# Mega2560_SX_Shield.net
KiCad netlist of a schematic drawn in EAGLE
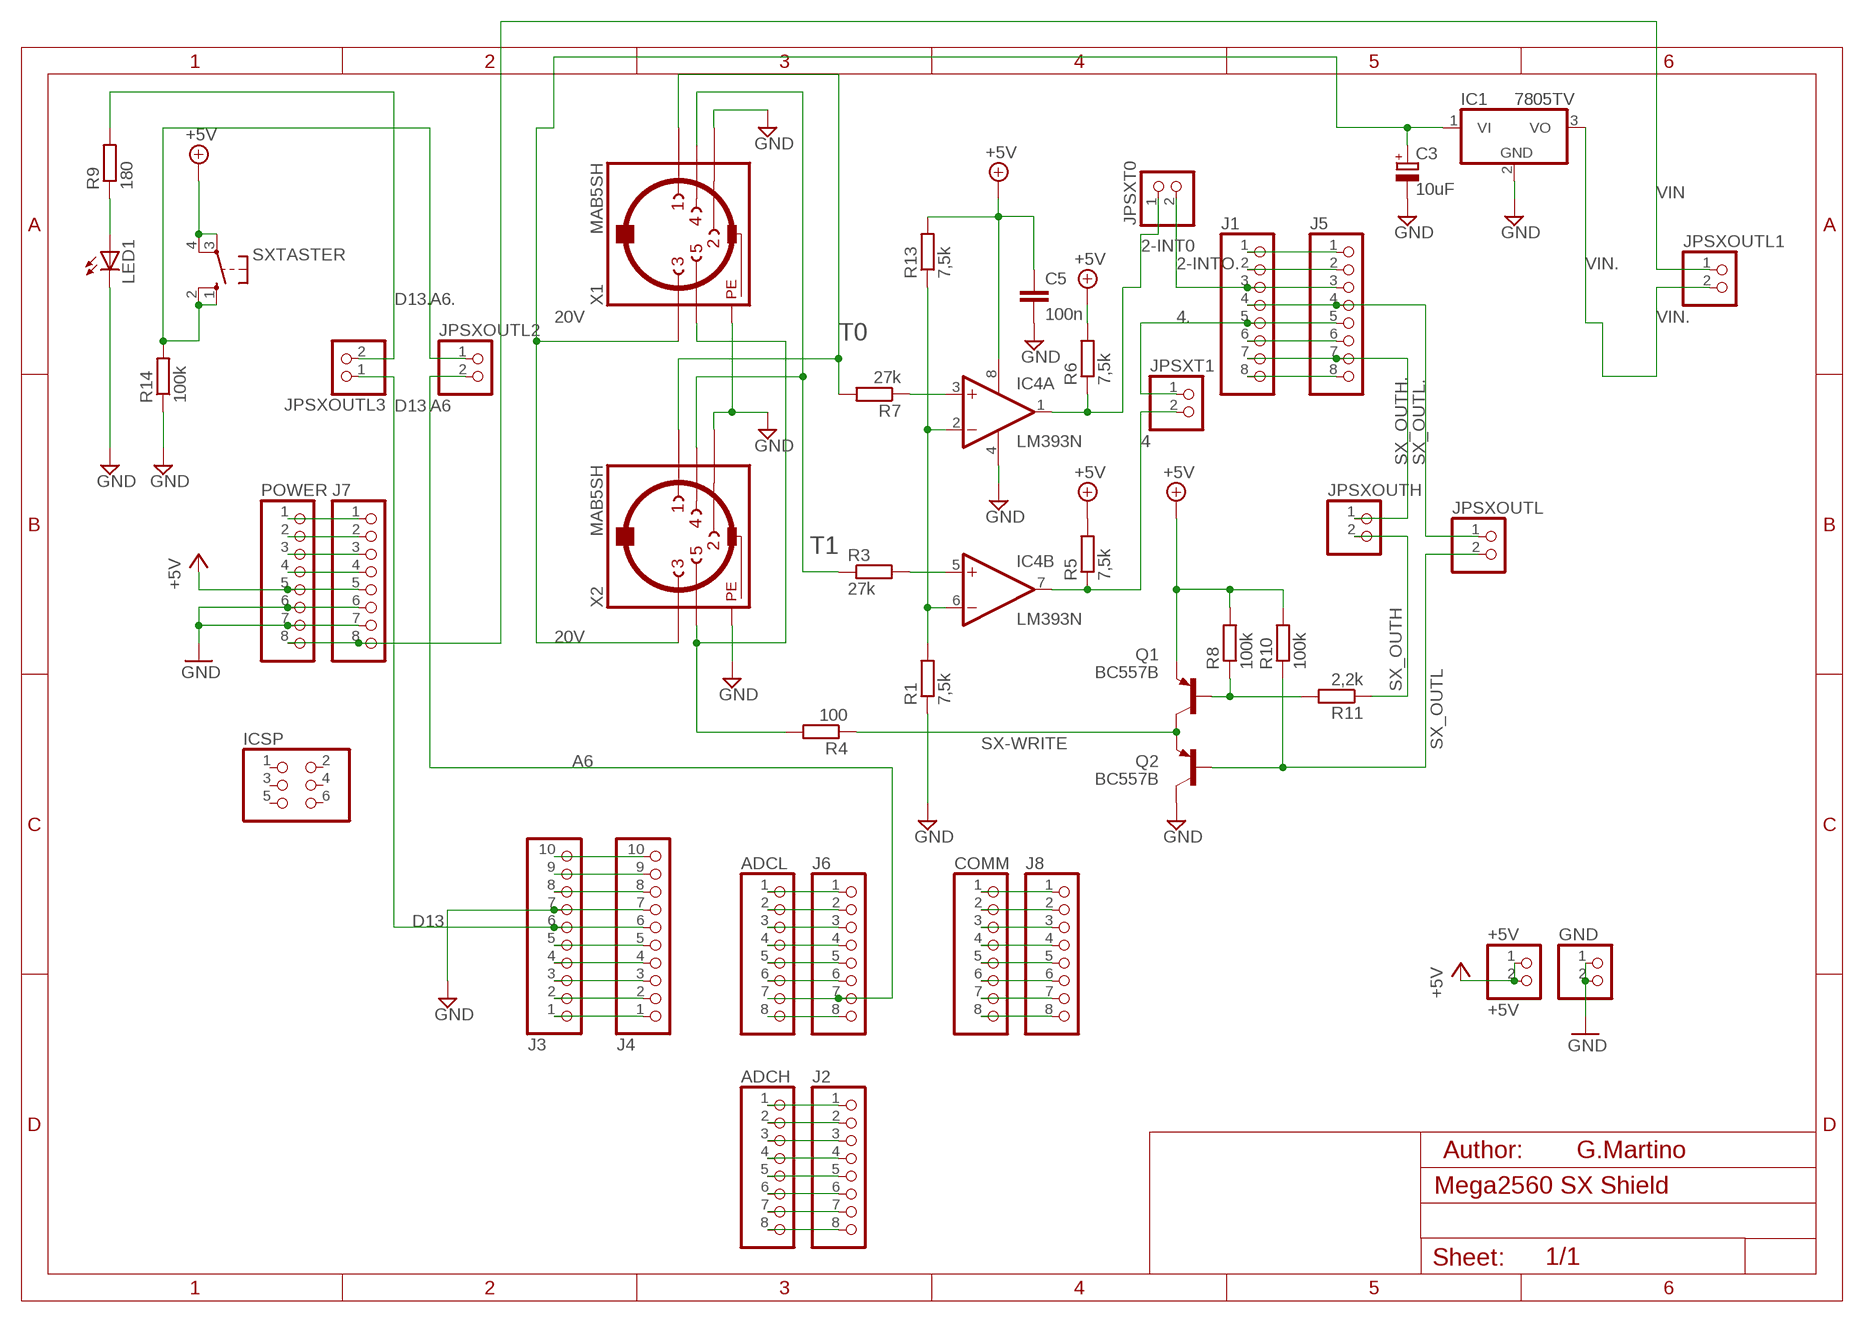
[diagram p0: schematic, sheet 1]

(export (version "E")
  (design (tool "Eeschema 10.0.6"))
  (components
    (comp (ref "+5V")
      (value "+5V")
      (footprint "eagle-import:1X02")
      (libsource (lib "eagle-import") (part "PINHD-1X2"))
    )
    (comp (ref "ADCH")
      (value "PINHD-1X8TH")
      (footprint "eagle-import:1X08-TH")
      (libsource (lib "eagle-import") (part "PINHD-1X8TH"))
    )
    (comp (ref "ADCL")
      (value "PINHD-1X8TH")
      (footprint "eagle-import:1X08-TH")
      (libsource (lib "eagle-import") (part "PINHD-1X8TH"))
    )
    (comp (ref "C3")
      (value "10uF")
      (footprint "eagle-import:TT2D5")
      (libsource (lib "eagle-import") (part "CPOL-EUTT2D5"))
    )
    (comp (ref "C5")
      (value "100n")
      (footprint "eagle-import:C050-025X075")
      (libsource (lib "eagle-import") (part "C-EU050-025X075"))
    )
    (comp (ref "COMM")
      (value "PINHD-1X8TH")
      (footprint "eagle-import:1X08-TH")
      (libsource (lib "eagle-import") (part "PINHD-1X8TH"))
    )
    (comp (ref "GND")
      (value "PINHD-1X2")
      (footprint "eagle-import:1X02")
      (libsource (lib "eagle-import") (part "PINHD-1X2"))
    )
    (comp (ref "IC1")
      (value "7805TV")
      (footprint "eagle-import:TO220V")
      (libsource (lib "eagle-import") (part "78TV05"))
    )
    (comp (ref "IC4")
      (value "LM393N")
      (footprint "eagle-import:DIL08")
      (libsource (lib "eagle-import") (part "LM393N"))
    )
    (comp (ref "ICSP")
      (value "PINHD-2X3")
      (footprint "eagle-import:2X03")
      (libsource (lib "eagle-import") (part "PINHD-2X3"))
    )
    (comp (ref "J1")
      (value "PINHD-1X8TH")
      (footprint "eagle-import:1X08-TH")
      (libsource (lib "eagle-import") (part "PINHD-1X8TH"))
    )
    (comp (ref "J2")
      (value "PINHD-1X8TH")
      (footprint "eagle-import:1X08-TH")
      (libsource (lib "eagle-import") (part "PINHD-1X8TH"))
    )
    (comp (ref "J3")
      (value "PINHD-1X10TH")
      (footprint "eagle-import:1X10-TH")
      (libsource (lib "eagle-import") (part "PINHD-1X10TH"))
    )
    (comp (ref "J4")
      (value "PINHD-1X10TH")
      (footprint "eagle-import:1X10-TH")
      (libsource (lib "eagle-import") (part "PINHD-1X10TH"))
    )
    (comp (ref "J5")
      (value "PINHD-1X8TH")
      (footprint "eagle-import:1X08-TH")
      (libsource (lib "eagle-import") (part "PINHD-1X8TH"))
    )
    (comp (ref "J6")
      (value "PINHD-1X8TH")
      (footprint "eagle-import:1X08-TH")
      (libsource (lib "eagle-import") (part "PINHD-1X8TH"))
    )
    (comp (ref "J7")
      (value "PINHD-1X8TH")
      (footprint "eagle-import:1X08-TH")
      (libsource (lib "eagle-import") (part "PINHD-1X8TH"))
    )
    (comp (ref "J8")
      (value "PINHD-1X8TH")
      (footprint "eagle-import:1X08-TH")
      (libsource (lib "eagle-import") (part "PINHD-1X8TH"))
    )
    (comp (ref "JPSXOUTH")
      (value "PINHD-1X2")
      (footprint "eagle-import:1X02")
      (libsource (lib "eagle-import") (part "PINHD-1X2"))
    )
    (comp (ref "JPSXOUTL")
      (value "PINHD-1X2")
      (footprint "eagle-import:1X02")
      (libsource (lib "eagle-import") (part "PINHD-1X2"))
    )
    (comp (ref "JPSXOUTL1")
      (value "PINHD-1X2")
      (footprint "eagle-import:1X02")
      (libsource (lib "eagle-import") (part "PINHD-1X2"))
    )
    (comp (ref "JPSXOUTL2")
      (value "PINHD-1X2")
      (footprint "eagle-import:1X02")
      (libsource (lib "eagle-import") (part "PINHD-1X2"))
    )
    (comp (ref "JPSXOUTL3")
      (value "PINHD-1X2")
      (footprint "eagle-import:1X02")
      (libsource (lib "eagle-import") (part "PINHD-1X2"))
    )
    (comp (ref "JPSXT0")
      (value "PINHD-1X2")
      (footprint "eagle-import:1X02")
      (libsource (lib "eagle-import") (part "PINHD-1X2"))
    )
    (comp (ref "JPSXT1")
      (value "PINHD-1X2")
      (footprint "eagle-import:1X02")
      (libsource (lib "eagle-import") (part "PINHD-1X2"))
    )
    (comp (ref "LED1")
      (value "LED3MM")
      (footprint "eagle-import:LED3MM")
      (libsource (lib "eagle-import") (part "LED3MM"))
    )
    (comp (ref "POWER")
      (value "PINHD-1X8TH")
      (footprint "eagle-import:1X08-TH")
      (libsource (lib "eagle-import") (part "PINHD-1X8TH"))
    )
    (comp (ref "Q1")
      (value "BC557B")
      (footprint "eagle-import:TO92-EBC")
      (libsource (lib "eagle-import") (part "BC557B"))
    )
    (comp (ref "Q2")
      (value "BC557B")
      (footprint "eagle-import:TO92-EBC")
      (libsource (lib "eagle-import") (part "BC557B"))
    )
    (comp (ref "R1")
      (value "7,5k")
      (footprint "eagle-import:0207_10")
      (libsource (lib "eagle-import") (part "rcl_334_R-EU_0207/10"))
    )
    (comp (ref "R3")
      (value "27k")
      (footprint "eagle-import:0207_10")
      (libsource (lib "eagle-import") (part "R-EU_0207/10"))
    )
    (comp (ref "R4")
      (value "100")
      (footprint "eagle-import:0207_10")
      (libsource (lib "eagle-import") (part "rcl_334_R-EU_0207/10"))
    )
    (comp (ref "R5")
      (value "7,5k")
      (footprint "eagle-import:0207_10")
      (libsource (lib "eagle-import") (part "rcl_334_R-EU_0207/10"))
    )
    (comp (ref "R6")
      (value "7,5k")
      (footprint "eagle-import:0207_10")
      (libsource (lib "eagle-import") (part "rcl_334_R-EU_0207/10"))
    )
    (comp (ref "R7")
      (value "27k")
      (footprint "eagle-import:0207_10")
      (libsource (lib "eagle-import") (part "rcl_334_R-EU_0207/10"))
    )
    (comp (ref "R8")
      (value "100k")
      (footprint "eagle-import:0207_10")
      (libsource (lib "eagle-import") (part "rcl_334_R-EU_0207/10"))
    )
    (comp (ref "R9")
      (value "180")
      (footprint "eagle-import:0207_10")
      (libsource (lib "eagle-import") (part "rcl_334_R-EU_0207/10"))
    )
    (comp (ref "R10")
      (value "100k")
      (footprint "eagle-import:0207_10")
      (libsource (lib "eagle-import") (part "rcl_334_R-EU_0207/10"))
    )
    (comp (ref "R11")
      (value "2,2k")
      (footprint "eagle-import:0207_10")
      (libsource (lib "eagle-import") (part "rcl_334_R-EU_0207/10"))
    )
    (comp (ref "R13")
      (value "7,5k")
      (footprint "eagle-import:0207_10")
      (libsource (lib "eagle-import") (part "rcl_334_R-EU_0207/10"))
    )
    (comp (ref "R14")
      (value "100k")
      (footprint "eagle-import:0207_10")
      (libsource (lib "eagle-import") (part "rcl_334_R-EU_0207/10"))
    )
    (comp (ref "SXTASTER")
      (value "10-XX")
      (footprint "eagle-import:B3F-10XX")
      (fields (field (name "MPN") "B3F-1000"))
      (libsource (lib "eagle-import") (part "10-XX"))
    )
    (comp (ref "X1")
      (value "MAB5SH")
      (footprint "eagle-import:MAB5SH")
      (libsource (lib "eagle-import") (part "MAB5SH"))
    )
    (comp (ref "X2")
      (value "MAB5SH")
      (footprint "eagle-import:MAB5SH")
      (libsource (lib "eagle-import") (part "MAB5SH"))
    )
  )
  (nets
    (net (code "1") (name "+5V") (class "Default")
      (node (ref "+5V") (pin "1") (pinfunction "1_1") (pintype "passive"))
      (node (ref "+5V") (pin "2") (pinfunction "2_2") (pintype "passive"))
      (node (ref "C5") (pin "1") (pinfunction "1_1") (pintype "passive"))
      (node (ref "IC4") (pin "8") (pinfunction "V+_8") (pintype "power_in"))
      (node (ref "J7") (pin "5") (pinfunction "5_5") (pintype "passive"))
      (node (ref "POWER") (pin "5") (pinfunction "5_5") (pintype "passive"))
      (node (ref "Q1") (pin "E") (pinfunction "E_E") (pintype "passive"))
      (node (ref "R10") (pin "2") (pinfunction "2_2") (pintype "passive"))
      (node (ref "R13") (pin "2") (pinfunction "2_2") (pintype "passive"))
      (node (ref "R5") (pin "2") (pinfunction "2_2") (pintype "passive"))
      (node (ref "R6") (pin "2") (pinfunction "2_2") (pintype "passive"))
      (node (ref "R8") (pin "2") (pinfunction "2_2") (pintype "passive"))
      (node (ref "SXTASTER") (pin "3") (pinfunction "P_3") (pintype "passive"))
      (node (ref "SXTASTER") (pin "4") (pinfunction "P1_4") (pintype "passive"))
    )
    (net (code "2") (name "/2-INT0") (class "Default")
      (node (ref "IC4") (pin "1") (pinfunction "OUT_1") (pintype "output"))
      (node (ref "JPSXT0") (pin "1") (pinfunction "1_1") (pintype "passive"))
      (node (ref "R6") (pin "1") (pinfunction "1_1") (pintype "passive"))
    )
    (net (code "3") (name "/2-INTO.") (class "Default")
      (node (ref "J1") (pin "3") (pinfunction "3_3") (pintype "passive"))
      (node (ref "J5") (pin "3") (pinfunction "3_3") (pintype "passive"))
      (node (ref "JPSXT0") (pin "2") (pinfunction "2_2") (pintype "passive"))
    )
    (net (code "4") (name "/4") (class "Default")
      (node (ref "IC4") (pin "7") (pinfunction "OUT_7") (pintype "output"))
      (node (ref "JPSXT1") (pin "2") (pinfunction "2_2") (pintype "passive"))
      (node (ref "R5") (pin "1") (pinfunction "1_1") (pintype "passive"))
    )
    (net (code "5") (name "/4.") (class "Default")
      (node (ref "J1") (pin "5") (pinfunction "5_5") (pintype "passive"))
      (node (ref "J5") (pin "5") (pinfunction "5_5") (pintype "passive"))
      (node (ref "JPSXT1") (pin "1") (pinfunction "1_1") (pintype "passive"))
    )
    (net (code "6") (name "/20V") (class "Default")
      (node (ref "C3") (pin "+") (pinfunction "+_+") (pintype "passive"))
      (node (ref "IC1") (pin "1") (pinfunction "VI_1") (pintype "input"))
      (node (ref "X1") (pin "3") (pinfunction "3_3") (pintype "passive"))
      (node (ref "X2") (pin "3") (pinfunction "3_3") (pintype "passive"))
    )
    (net (code "7") (name "/A6") (class "Default")
      (node (ref "ADCL") (pin "7") (pinfunction "7_7") (pintype "passive"))
      (node (ref "J6") (pin "7") (pinfunction "7_7") (pintype "passive"))
      (node (ref "JPSXOUTL2") (pin "2") (pinfunction "2_2") (pintype "passive"))
    )
    (net (code "8") (name "/A6.") (class "Default")
      (node (ref "JPSXOUTL2") (pin "1") (pinfunction "1_1") (pintype "passive"))
      (node (ref "R14") (pin "2") (pinfunction "2_2") (pintype "passive"))
      (node (ref "SXTASTER") (pin "1") (pinfunction "S_1") (pintype "passive"))
      (node (ref "SXTASTER") (pin "2") (pinfunction "S1_2") (pintype "passive"))
    )
    (net (code "9") (name "/D13") (class "Default")
      (node (ref "J3") (pin "6") (pinfunction "6_6") (pintype "passive"))
      (node (ref "J4") (pin "6") (pinfunction "6_6") (pintype "passive"))
      (node (ref "JPSXOUTL3") (pin "1") (pinfunction "1_1") (pintype "passive"))
    )
    (net (code "10") (name "/D13.") (class "Default")
      (node (ref "JPSXOUTL3") (pin "2") (pinfunction "2_2") (pintype "passive"))
      (node (ref "R9") (pin "2") (pinfunction "2_2") (pintype "passive"))
    )
    (net (code "11") (name "/SX-WRITE") (class "Default")
      (node (ref "Q1") (pin "C") (pinfunction "C_C") (pintype "passive"))
      (node (ref "Q2") (pin "E") (pinfunction "E_E") (pintype "passive"))
      (node (ref "R4") (pin "1") (pinfunction "1_1") (pintype "passive"))
    )
    (net (code "12") (name "/SX_OUTH") (class "Default")
      (node (ref "JPSXOUTH") (pin "2") (pinfunction "2_2") (pintype "passive"))
      (node (ref "R11") (pin "1") (pinfunction "1_1") (pintype "passive"))
    )
    (net (code "13") (name "/SX_OUTH.") (class "Default")
      (node (ref "J1") (pin "7") (pinfunction "7_7") (pintype "passive"))
      (node (ref "J5") (pin "7") (pinfunction "7_7") (pintype "passive"))
      (node (ref "JPSXOUTH") (pin "1") (pinfunction "1_1") (pintype "passive"))
    )
    (net (code "14") (name "/SX_OUTL") (class "Default")
      (node (ref "JPSXOUTL") (pin "2") (pinfunction "2_2") (pintype "passive"))
      (node (ref "Q2") (pin "B") (pinfunction "B_B") (pintype "passive"))
      (node (ref "R10") (pin "1") (pinfunction "1_1") (pintype "passive"))
    )
    (net (code "15") (name "/SX_OUTL.") (class "Default")
      (node (ref "J1") (pin "4") (pinfunction "4_4") (pintype "passive"))
      (node (ref "J5") (pin "4") (pinfunction "4_4") (pintype "passive"))
      (node (ref "JPSXOUTL") (pin "1") (pinfunction "1_1") (pintype "passive"))
    )
    (net (code "16") (name "/T0") (class "Default")
      (node (ref "R7") (pin "2") (pinfunction "2_2") (pintype "passive"))
      (node (ref "X1") (pin "1") (pinfunction "1_1") (pintype "passive"))
      (node (ref "X2") (pin "1") (pinfunction "1_1") (pintype "passive"))
    )
    (net (code "17") (name "/T1") (class "Default")
      (node (ref "R3") (pin "1") (pinfunction "1_1") (pintype "passive"))
      (node (ref "X1") (pin "4") (pinfunction "4_4") (pintype "passive"))
      (node (ref "X2") (pin "4") (pinfunction "4_4") (pintype "passive"))
    )
    (net (code "18") (name "/VIN") (class "Default")
      (node (ref "J7") (pin "8") (pinfunction "8_8") (pintype "passive"))
      (node (ref "JPSXOUTL1") (pin "1") (pinfunction "1_1") (pintype "passive"))
      (node (ref "POWER") (pin "8") (pinfunction "8_8") (pintype "passive"))
    )
    (net (code "19") (name "/VIN.") (class "Default")
      (node (ref "IC1") (pin "3") (pinfunction "VO_3") (pintype "passive"))
      (node (ref "JPSXOUTL1") (pin "2") (pinfunction "2_2") (pintype "passive"))
    )
    (net (code "20") (name "GND") (class "Default")
      (node (ref "C3") (pin "-") (pinfunction "-_-") (pintype "passive"))
      (node (ref "C5") (pin "2") (pinfunction "2_2") (pintype "passive"))
      (node (ref "GND") (pin "1") (pinfunction "1_1") (pintype "passive"))
      (node (ref "GND") (pin "2") (pinfunction "2_2") (pintype "passive"))
      (node (ref "IC1") (pin "2") (pinfunction "GND_2") (pintype "passive"))
      (node (ref "IC4") (pin "4") (pinfunction "V-_4") (pintype "power_in"))
      (node (ref "J3") (pin "7") (pinfunction "7_7") (pintype "passive"))
      (node (ref "J4") (pin "7") (pinfunction "7_7") (pintype "passive"))
      (node (ref "J7") (pin "6") (pinfunction "6_6") (pintype "passive"))
      (node (ref "J7") (pin "7") (pinfunction "7_7") (pintype "passive"))
      (node (ref "LED1") (pin "K") (pinfunction "C_K") (pintype "passive"))
      (node (ref "POWER") (pin "6") (pinfunction "6_6") (pintype "passive"))
      (node (ref "POWER") (pin "7") (pinfunction "7_7") (pintype "passive"))
      (node (ref "Q2") (pin "C") (pinfunction "C_C") (pintype "passive"))
      (node (ref "R1") (pin "1") (pinfunction "1_1") (pintype "passive"))
      (node (ref "R14") (pin "1") (pinfunction "1_1") (pintype "passive"))
      (node (ref "X1") (pin "2") (pinfunction "2_2") (pintype "passive"))
      (node (ref "X1") (pin "PE") (pinfunction "PE_PE") (pintype "power_in"))
      (node (ref "X1") (pin "PE@") (pinfunction "PE_PE@") (pintype "power_in"))
      (node (ref "X1") (pin "PE@1") (pinfunction "PE_PE@1") (pintype "power_in"))
      (node (ref "X1") (pin "PE@2") (pinfunction "PE_PE@2") (pintype "power_in"))
      (node (ref "X2") (pin "2") (pinfunction "2_2") (pintype "passive"))
      (node (ref "X2") (pin "PE") (pinfunction "PE_PE") (pintype "power_in"))
      (node (ref "X2") (pin "PE@") (pinfunction "PE_PE@") (pintype "power_in"))
      (node (ref "X2") (pin "PE@1") (pinfunction "PE_PE@1") (pintype "power_in"))
      (node (ref "X2") (pin "PE@2") (pinfunction "PE_PE@2") (pintype "power_in"))
    )
    (net (code "21") (name "Net-(ADCH-Pad1)") (class "Default")
      (node (ref "ADCH") (pin "1") (pinfunction "1_1") (pintype "passive"))
      (node (ref "J2") (pin "1") (pinfunction "1_1") (pintype "passive"))
    )
    (net (code "22") (name "Net-(ADCH-Pad2)") (class "Default")
      (node (ref "ADCH") (pin "2") (pinfunction "2_2") (pintype "passive"))
      (node (ref "J2") (pin "2") (pinfunction "2_2") (pintype "passive"))
    )
    (net (code "23") (name "Net-(ADCH-Pad3)") (class "Default")
      (node (ref "ADCH") (pin "3") (pinfunction "3_3") (pintype "passive"))
      (node (ref "J2") (pin "3") (pinfunction "3_3") (pintype "passive"))
    )
    (net (code "24") (name "Net-(ADCH-Pad4)") (class "Default")
      (node (ref "ADCH") (pin "4") (pinfunction "4_4") (pintype "passive"))
      (node (ref "J2") (pin "4") (pinfunction "4_4") (pintype "passive"))
    )
    (net (code "25") (name "Net-(ADCH-Pad5)") (class "Default")
      (node (ref "ADCH") (pin "5") (pinfunction "5_5") (pintype "passive"))
      (node (ref "J2") (pin "5") (pinfunction "5_5") (pintype "passive"))
    )
    (net (code "26") (name "Net-(ADCH-Pad6)") (class "Default")
      (node (ref "ADCH") (pin "6") (pinfunction "6_6") (pintype "passive"))
      (node (ref "J2") (pin "6") (pinfunction "6_6") (pintype "passive"))
    )
    (net (code "27") (name "Net-(ADCH-Pad7)") (class "Default")
      (node (ref "ADCH") (pin "7") (pinfunction "7_7") (pintype "passive"))
      (node (ref "J2") (pin "7") (pinfunction "7_7") (pintype "passive"))
    )
    (net (code "28") (name "Net-(ADCH-Pad8)") (class "Default")
      (node (ref "ADCH") (pin "8") (pinfunction "8_8") (pintype "passive"))
      (node (ref "J2") (pin "8") (pinfunction "8_8") (pintype "passive"))
    )
    (net (code "29") (name "Net-(ADCL-Pad1)") (class "Default")
      (node (ref "ADCL") (pin "1") (pinfunction "1_1") (pintype "passive"))
      (node (ref "J6") (pin "1") (pinfunction "1_1") (pintype "passive"))
    )
    (net (code "30") (name "Net-(ADCL-Pad2)") (class "Default")
      (node (ref "ADCL") (pin "2") (pinfunction "2_2") (pintype "passive"))
      (node (ref "J6") (pin "2") (pinfunction "2_2") (pintype "passive"))
    )
    (net (code "31") (name "Net-(ADCL-Pad3)") (class "Default")
      (node (ref "ADCL") (pin "3") (pinfunction "3_3") (pintype "passive"))
      (node (ref "J6") (pin "3") (pinfunction "3_3") (pintype "passive"))
    )
    (net (code "32") (name "Net-(ADCL-Pad4)") (class "Default")
      (node (ref "ADCL") (pin "4") (pinfunction "4_4") (pintype "passive"))
      (node (ref "J6") (pin "4") (pinfunction "4_4") (pintype "passive"))
    )
    (net (code "33") (name "Net-(ADCL-Pad5)") (class "Default")
      (node (ref "ADCL") (pin "5") (pinfunction "5_5") (pintype "passive"))
      (node (ref "J6") (pin "5") (pinfunction "5_5") (pintype "passive"))
    )
    (net (code "34") (name "Net-(ADCL-Pad6)") (class "Default")
      (node (ref "ADCL") (pin "6") (pinfunction "6_6") (pintype "passive"))
      (node (ref "J6") (pin "6") (pinfunction "6_6") (pintype "passive"))
    )
    (net (code "35") (name "Net-(ADCL-Pad8)") (class "Default")
      (node (ref "ADCL") (pin "8") (pinfunction "8_8") (pintype "passive"))
      (node (ref "J6") (pin "8") (pinfunction "8_8") (pintype "passive"))
    )
    (net (code "36") (name "Net-(COMM-Pad1)") (class "Default")
      (node (ref "COMM") (pin "1") (pinfunction "1_1") (pintype "passive"))
      (node (ref "J8") (pin "1") (pinfunction "1_1") (pintype "passive"))
    )
    (net (code "37") (name "Net-(COMM-Pad2)") (class "Default")
      (node (ref "COMM") (pin "2") (pinfunction "2_2") (pintype "passive"))
      (node (ref "J8") (pin "2") (pinfunction "2_2") (pintype "passive"))
    )
    (net (code "38") (name "Net-(COMM-Pad3)") (class "Default")
      (node (ref "COMM") (pin "3") (pinfunction "3_3") (pintype "passive"))
      (node (ref "J8") (pin "3") (pinfunction "3_3") (pintype "passive"))
    )
    (net (code "39") (name "Net-(COMM-Pad4)") (class "Default")
      (node (ref "COMM") (pin "4") (pinfunction "4_4") (pintype "passive"))
      (node (ref "J8") (pin "4") (pinfunction "4_4") (pintype "passive"))
    )
    (net (code "40") (name "Net-(COMM-Pad5)") (class "Default")
      (node (ref "COMM") (pin "5") (pinfunction "5_5") (pintype "passive"))
      (node (ref "J8") (pin "5") (pinfunction "5_5") (pintype "passive"))
    )
    (net (code "41") (name "Net-(COMM-Pad6)") (class "Default")
      (node (ref "COMM") (pin "6") (pinfunction "6_6") (pintype "passive"))
      (node (ref "J8") (pin "6") (pinfunction "6_6") (pintype "passive"))
    )
    (net (code "42") (name "Net-(COMM-Pad7)") (class "Default")
      (node (ref "COMM") (pin "7") (pinfunction "7_7") (pintype "passive"))
      (node (ref "J8") (pin "7") (pinfunction "7_7") (pintype "passive"))
    )
    (net (code "43") (name "Net-(COMM-Pad8)") (class "Default")
      (node (ref "COMM") (pin "8") (pinfunction "8_8") (pintype "passive"))
      (node (ref "J8") (pin "8") (pinfunction "8_8") (pintype "passive"))
    )
    (net (code "44") (name "Net-(IC4A-+IN)") (class "Default")
      (node (ref "IC4") (pin "3") (pinfunction "+IN_3") (pintype "input"))
      (node (ref "R7") (pin "1") (pinfunction "1_1") (pintype "passive"))
    )
    (net (code "45") (name "Net-(IC4A--IN)") (class "Default")
      (node (ref "IC4") (pin "2") (pinfunction "-IN_2") (pintype "input"))
      (node (ref "IC4") (pin "6") (pinfunction "-IN_6") (pintype "input"))
      (node (ref "R1") (pin "2") (pinfunction "2_2") (pintype "passive"))
      (node (ref "R13") (pin "1") (pinfunction "1_1") (pintype "passive"))
    )
    (net (code "46") (name "Net-(IC4B-+IN)") (class "Default")
      (node (ref "IC4") (pin "5") (pinfunction "+IN_5") (pintype "input"))
      (node (ref "R3") (pin "2") (pinfunction "2_2") (pintype "passive"))
    )
    (net (code "47") (name "Net-(J1-Pad1)") (class "Default")
      (node (ref "J1") (pin "1") (pinfunction "1_1") (pintype "passive"))
      (node (ref "J5") (pin "1") (pinfunction "1_1") (pintype "passive"))
    )
    (net (code "48") (name "Net-(J1-Pad2)") (class "Default")
      (node (ref "J1") (pin "2") (pinfunction "2_2") (pintype "passive"))
      (node (ref "J5") (pin "2") (pinfunction "2_2") (pintype "passive"))
    )
    (net (code "49") (name "Net-(J1-Pad6)") (class "Default")
      (node (ref "J1") (pin "6") (pinfunction "6_6") (pintype "passive"))
      (node (ref "J5") (pin "6") (pinfunction "6_6") (pintype "passive"))
    )
    (net (code "50") (name "Net-(J1-Pad8)") (class "Default")
      (node (ref "J1") (pin "8") (pinfunction "8_8") (pintype "passive"))
      (node (ref "J5") (pin "8") (pinfunction "8_8") (pintype "passive"))
    )
    (net (code "51") (name "Net-(J3-Pad1)") (class "Default")
      (node (ref "J3") (pin "1") (pinfunction "1_1") (pintype "passive"))
      (node (ref "J4") (pin "1") (pinfunction "1_1") (pintype "passive"))
    )
    (net (code "52") (name "Net-(J3-Pad2)") (class "Default")
      (node (ref "J3") (pin "2") (pinfunction "2_2") (pintype "passive"))
      (node (ref "J4") (pin "2") (pinfunction "2_2") (pintype "passive"))
    )
    (net (code "53") (name "Net-(J3-Pad3)") (class "Default")
      (node (ref "J3") (pin "3") (pinfunction "3_3") (pintype "passive"))
      (node (ref "J4") (pin "3") (pinfunction "3_3") (pintype "passive"))
    )
    (net (code "54") (name "Net-(J3-Pad4)") (class "Default")
      (node (ref "J3") (pin "4") (pinfunction "4_4") (pintype "passive"))
      (node (ref "J4") (pin "4") (pinfunction "4_4") (pintype "passive"))
    )
    (net (code "55") (name "Net-(J3-Pad5)") (class "Default")
      (node (ref "J3") (pin "5") (pinfunction "5_5") (pintype "passive"))
      (node (ref "J4") (pin "5") (pinfunction "5_5") (pintype "passive"))
    )
    (net (code "56") (name "Net-(J3-Pad8)") (class "Default")
      (node (ref "J3") (pin "8") (pinfunction "8_8") (pintype "passive"))
      (node (ref "J4") (pin "8") (pinfunction "8_8") (pintype "passive"))
    )
    (net (code "57") (name "Net-(J3-Pad9)") (class "Default")
      (node (ref "J3") (pin "9") (pinfunction "9_9") (pintype "passive"))
      (node (ref "J4") (pin "9") (pinfunction "9_9") (pintype "passive"))
    )
    (net (code "58") (name "Net-(J3-Pad10)") (class "Default")
      (node (ref "J3") (pin "10") (pinfunction "10_10") (pintype "passive"))
      (node (ref "J4") (pin "10") (pinfunction "10_10") (pintype "passive"))
    )
    (net (code "59") (name "Net-(J7-Pad1)") (class "Default")
      (node (ref "J7") (pin "1") (pinfunction "1_1") (pintype "passive"))
      (node (ref "POWER") (pin "1") (pinfunction "1_1") (pintype "passive"))
    )
    (net (code "60") (name "Net-(J7-Pad2)") (class "Default")
      (node (ref "J7") (pin "2") (pinfunction "2_2") (pintype "passive"))
      (node (ref "POWER") (pin "2") (pinfunction "2_2") (pintype "passive"))
    )
    (net (code "61") (name "Net-(J7-Pad3)") (class "Default")
      (node (ref "J7") (pin "3") (pinfunction "3_3") (pintype "passive"))
      (node (ref "POWER") (pin "3") (pinfunction "3_3") (pintype "passive"))
    )
    (net (code "62") (name "Net-(J7-Pad4)") (class "Default")
      (node (ref "J7") (pin "4") (pinfunction "4_4") (pintype "passive"))
      (node (ref "POWER") (pin "4") (pinfunction "4_4") (pintype "passive"))
    )
    (net (code "63") (name "Net-(LED1-PadA)") (class "Default")
      (node (ref "LED1") (pin "A") (pinfunction "A_A") (pintype "passive"))
      (node (ref "R9") (pin "1") (pinfunction "1_1") (pintype "passive"))
    )
    (net (code "64") (name "Net-(Q1-PadB)") (class "Default")
      (node (ref "Q1") (pin "B") (pinfunction "B_B") (pintype "passive"))
      (node (ref "R11") (pin "2") (pinfunction "2_2") (pintype "passive"))
      (node (ref "R8") (pin "1") (pinfunction "1_1") (pintype "passive"))
    )
    (net (code "65") (name "Net-(R4-Pad2)") (class "Default")
      (node (ref "R4") (pin "2") (pinfunction "2_2") (pintype "passive"))
      (node (ref "X1") (pin "5") (pinfunction "5_5") (pintype "passive"))
      (node (ref "X2") (pin "5") (pinfunction "5_5") (pintype "passive"))
    )
    (net (code "66") (name "unconnected-(ICSP-Pad1)") (class "Default")
      (node (ref "ICSP") (pin "1") (pinfunction "1_1") (pintype "passive"))
    )
    (net (code "67") (name "unconnected-(ICSP-Pad2)") (class "Default")
      (node (ref "ICSP") (pin "2") (pinfunction "2_2") (pintype "passive"))
    )
    (net (code "68") (name "unconnected-(ICSP-Pad3)") (class "Default")
      (node (ref "ICSP") (pin "3") (pinfunction "3_3") (pintype "passive"))
    )
    (net (code "69") (name "unconnected-(ICSP-Pad4)") (class "Default")
      (node (ref "ICSP") (pin "4") (pinfunction "4_4") (pintype "passive"))
    )
    (net (code "70") (name "unconnected-(ICSP-Pad5)") (class "Default")
      (node (ref "ICSP") (pin "5") (pinfunction "5_5") (pintype "passive"))
    )
    (net (code "71") (name "unconnected-(ICSP-Pad6)") (class "Default")
      (node (ref "ICSP") (pin "6") (pinfunction "6_6") (pintype "passive"))
    )
  )
)
